# 468262_004_3_2.net
KiCad netlist of a schematic drawn in Altium Designer
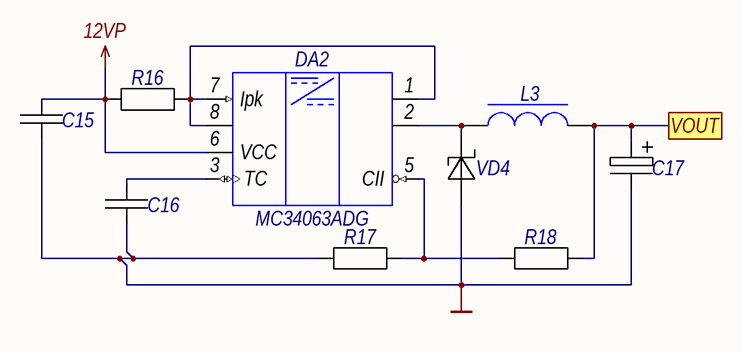
[diagram p0: ШЮГИ.468262.004 Э3 Л2.SchDoc]

(export (version "E")
  (design (tool "Eeschema 10.0.6"))
  (components
    (comp (ref "C15")
      (value "0603B104J500CT Thunder")
      (footprint "C0603")
      (fields (field (name "PART NUMBER") "0603B104J500CT") (field (name "POWER") "50 V"))
      (libsource (lib "Конденсаторы танталовые") (part "cap"))
    )
    (comp (ref "C16")
      (value "0603B561J500CT Thunder")
      (footprint "C0603")
      (fields (field (name "PART NUMBER") "0603B561J500CT") (field (name "POWER") "50 V"))
      (libsource (lib "Конденсаторы танталовые") (part "cap"))
    )
    (comp (ref "C17")
      (value "JCK1C100M040054 JB Capacitors")
      (footprint "AL4X54")
      (fields (field (name "PART NUMBER") "JCK1C100M040054") (field (name "POWER") "16 V"))
      (libsource (lib "Конденсаторы танталовые") (part "elcap"))
    )
    (comp (ref "DA2")
      (value "MC34063ADG")
      (footprint "SO-8")
      (libsource (lib "Микроконтроллеры") (part "MC34063"))
    )
    (comp (ref "L3")
      (value "CDRH74NP-101MC-B SUMIDA CORPORATION")
      (footprint "INDP7373X45N")
      (fields (field (name "PART NUMBER") "CDRH74NP-101MC-B"))
      (libsource (lib "IND SUMIDA$") (part "CDRH74NP-101MC-B"))
    )
    (comp (ref "R16")
      (value "CRL1206-FW-R220ELF Bourns")
      (footprint "R1206")
      (fields (field (name "PART NUMBER") "CRL1206-FW-R220ELF") (field (name "POWER") "0,25 Вт"))
      (libsource (lib "Конденсаторы танталовые") (part "res"))
    )
    (comp (ref "R17")
      (value "Р1-12-0,25-1,21 кОм±2 %-Т-Л-М АБШК.434110.023 ТУ")
      (footprint "R1206")
      (fields (field (name "PART NUMBER") "Р1-12-0,25-1,21 кОм±2 %-Т-Л-М") (field (name "POWER") "0,25"))
      (libsource (lib "Конденсаторы танталовые") (part "res"))
    )
    (comp (ref "R18")
      (value "Р1-12-0,25-3,65 кОм±2 %-Т-Л-М АБШК.434110.023 ТУ")
      (footprint "R1206")
      (fields (field (name "PART NUMBER") "Р1-12-0,25-3,65 кОм±2 %-Т-Л-М") (field (name "POWER") "0,25"))
      (libsource (lib "Конденсаторы танталовые") (part "res"))
    )
    (comp (ref "VD4")
      (value "10MQ040 Sunmate Electronics")
      (footprint "DO-214AC")
      (description "Диод Шоттки")
      (fields (field (name "PART NUMBER") "10MQ040"))
      (libsource (lib "Диоды и транзисторы") (part "Shottky_diode"))
    )
  )
  (nets
    (net (code "1") (name "/VOUT") (class "Default")
      (node (ref "C17") (pin "1") (pinfunction "+_1") (pintype "passive"))
      (node (ref "L3") (pin "2") (pinfunction "2_2") (pintype "passive"))
      (node (ref "R18") (pin "2") (pinfunction "2_2") (pintype "passive"))
    )
    (net (code "2") (name "12VP") (class "Default")
      (node (ref "C15") (pin "1") (pinfunction "1_1") (pintype "passive"))
      (node (ref "DA2") (pin "6") (pinfunction "VCC_6") (pintype "power_in"))
      (node (ref "R16") (pin "1") (pinfunction "+_1") (pintype "passive"))
    )
    (net (code "3") (name "GND") (class "Default")
      (node (ref "C15") (pin "2") (pinfunction "2_2") (pintype "passive"))
      (node (ref "C16") (pin "2") (pinfunction "2_2") (pintype "passive"))
      (node (ref "C17") (pin "2") (pinfunction "2_2") (pintype "passive"))
      (node (ref "DA2") (pin "4") (pinfunction "GND_4") (pintype "power_in"))
      (node (ref "R17") (pin "1") (pinfunction "+_1") (pintype "passive"))
      (node (ref "VD4") (pin "1") (pinfunction "AN_1") (pintype "passive"))
    )
    (net (code "4") (name "Net-(DA2-C)") (class "Default")
      (node (ref "DA2") (pin "1") (pinfunction "C_1") (pintype "open_collector"))
      (node (ref "DA2") (pin "7") (pinfunction "Ipk_7") (pintype "input"))
      (node (ref "DA2") (pin "8") (pinfunction "DC_8") (pintype "open_collector"))
      (node (ref "R16") (pin "2") (pinfunction "2_2") (pintype "passive"))
    )
    (net (code "5") (name "Net-(DA2-CII)") (class "Default")
      (node (ref "DA2") (pin "5") (pinfunction "CII_5") (pintype "input"))
      (node (ref "R17") (pin "2") (pinfunction "2_2") (pintype "passive"))
      (node (ref "R18") (pin "1") (pinfunction "+_1") (pintype "passive"))
    )
    (net (code "6") (name "Net-(DA2-E)") (class "Default")
      (node (ref "DA2") (pin "2") (pinfunction "E_2") (pintype "open_emitter"))
      (node (ref "L3") (pin "1") (pinfunction "1_1") (pintype "passive"))
      (node (ref "VD4") (pin "2") (pinfunction "CT_2") (pintype "passive"))
    )
    (net (code "7") (name "Net-(DA2-TC)") (class "Default")
      (node (ref "C16") (pin "1") (pinfunction "1_1") (pintype "passive"))
      (node (ref "DA2") (pin "3") (pinfunction "TC_3") (pintype "bidirectional"))
    )
  )
)
